# 4_2in_display.net
KiCad netlist of a schematic drawn in EAGLE
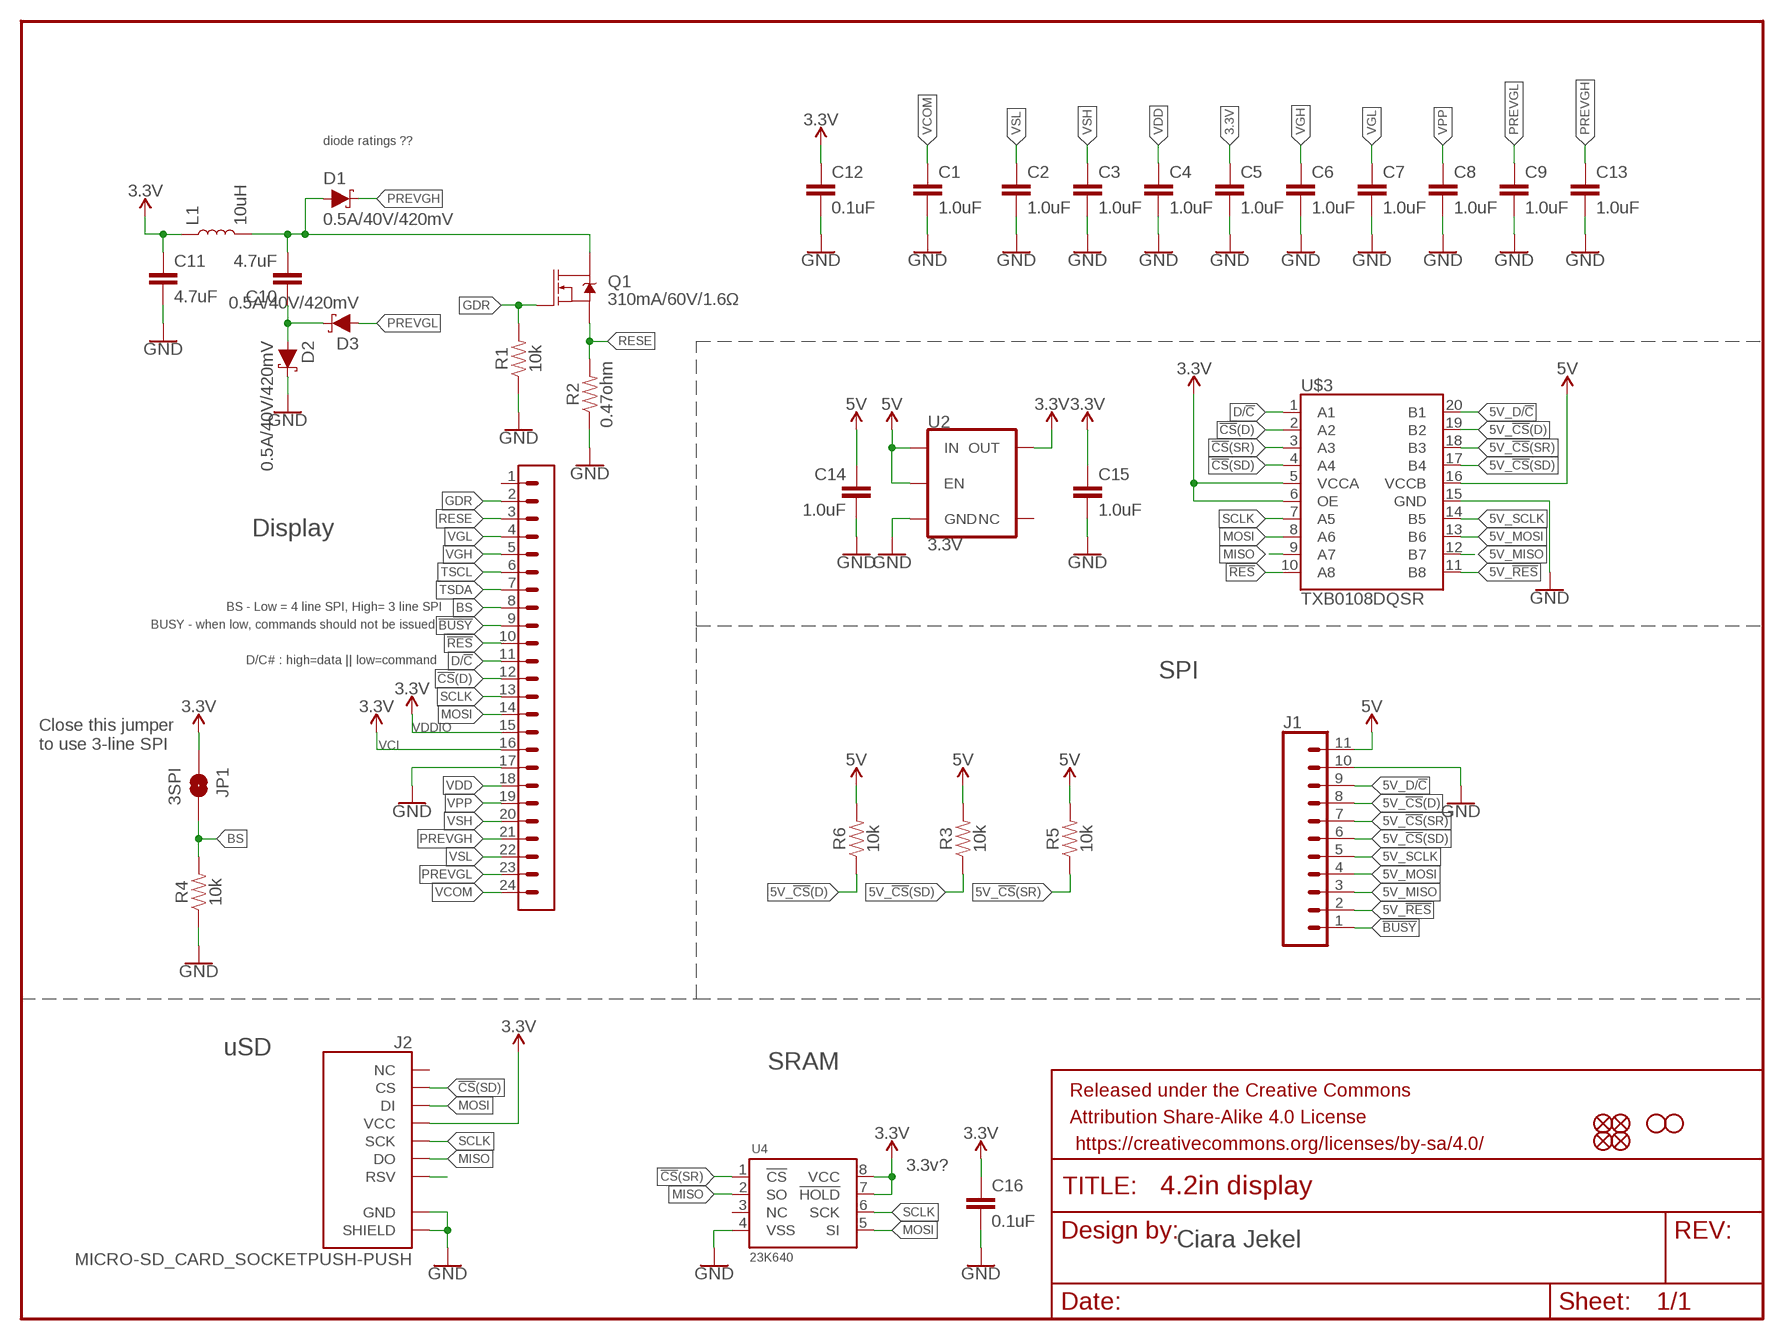
[diagram p0: schematic, sheet 1]

(export (version "E")
  (design (tool "Eeschema 10.0.6"))
  (components
    (comp (ref "C1")
      (value "1.0uF")
      (footprint "eagle-import:0603")
      (libsource (lib "eagle-import") (part "1.0UF-0603-16V-10%"))
    )
    (comp (ref "C2")
      (value "1.0uF")
      (footprint "eagle-import:0805")
      (libsource (lib "eagle-import") (part "1.0UF-0805-25V-10%"))
    )
    (comp (ref "C3")
      (value "1.0uF")
      (footprint "eagle-import:0805")
      (libsource (lib "eagle-import") (part "1.0UF-0805-25V-10%"))
    )
    (comp (ref "C4")
      (value "1.0uF")
      (footprint "eagle-import:0805")
      (libsource (lib "eagle-import") (part "1.0UF-0805-25V-10%"))
    )
    (comp (ref "C5")
      (value "1.0uF")
      (footprint "eagle-import:0805")
      (libsource (lib "eagle-import") (part "1.0UF-0805-25V-10%"))
    )
    (comp (ref "C6")
      (value "1.0uF")
      (footprint "eagle-import:0805")
      (libsource (lib "eagle-import") (part "1.0UF-0805-25V-10%"))
    )
    (comp (ref "C7")
      (value "1.0uF")
      (footprint "eagle-import:0805")
      (libsource (lib "eagle-import") (part "1.0UF-0805-25V-10%"))
    )
    (comp (ref "C8")
      (value "1.0uF")
      (footprint "eagle-import:0805")
      (libsource (lib "eagle-import") (part "1.0UF-0805-25V-10%"))
    )
    (comp (ref "C9")
      (value "1.0uF")
      (footprint "eagle-import:0805")
      (libsource (lib "eagle-import") (part "1.0UF-0805-25V-10%"))
    )
    (comp (ref "C10")
      (value "4.7uF")
      (footprint "eagle-import:0805")
      (libsource (lib "eagle-import") (part "22UF-0805-6.3V-20%"))
    )
    (comp (ref "C11")
      (value "4.7uF")
      (footprint "eagle-import:0805")
      (libsource (lib "eagle-import") (part "22UF-0805-6.3V-20%"))
    )
    (comp (ref "C12")
      (value "0.1uF")
      (footprint "eagle-import:0603")
      (libsource (lib "eagle-import") (part "0.1UF-0603-25V-(+80/-20%)"))
    )
    (comp (ref "C13")
      (value "1.0uF")
      (footprint "eagle-import:0805")
      (libsource (lib "eagle-import") (part "1.0UF-0805-25V-10%"))
    )
    (comp (ref "C14")
      (value "1.0uF")
      (footprint "eagle-import:0603")
      (libsource (lib "eagle-import") (part "1.0UF-0603-16V-10%"))
    )
    (comp (ref "C15")
      (value "1.0uF")
      (footprint "eagle-import:0603")
      (libsource (lib "eagle-import") (part "1.0UF-0603-16V-10%"))
    )
    (comp (ref "C16")
      (value "0.1uF")
      (footprint "eagle-import:0603")
      (libsource (lib "eagle-import") (part "0.1UF-0603-25V-(+80/-20%)"))
    )
    (comp (ref "D1")
      (value "0.5A/40V/420mV")
      (footprint "eagle-import:SOD-323")
      (libsource (lib "eagle-import") (part "DIODE-SCHOTTKY-PMEG4005EJ"))
    )
    (comp (ref "D2")
      (value "0.5A/40V/420mV")
      (footprint "eagle-import:SOD-323")
      (libsource (lib "eagle-import") (part "DIODE-SCHOTTKY-PMEG4005EJ"))
    )
    (comp (ref "D3")
      (value "0.5A/40V/420mV")
      (footprint "eagle-import:SOD-323")
      (libsource (lib "eagle-import") (part "DIODE-SCHOTTKY-PMEG4005EJ"))
    )
    (comp (ref "FD1")
      (value "FIDUCIALUFIDUCIAL")
      (footprint "eagle-import:FIDUCIAL-MICRO")
      (libsource (lib "eagle-import") (part "FIDUCIALUFIDUCIAL"))
    )
    (comp (ref "FD2")
      (value "FIDUCIALUFIDUCIAL")
      (footprint "eagle-import:FIDUCIAL-MICRO")
      (libsource (lib "eagle-import") (part "FIDUCIALUFIDUCIAL"))
    )
    (comp (ref "FD3")
      (value "FIDUCIALUFIDUCIAL")
      (footprint "eagle-import:FIDUCIAL-MICRO")
      (libsource (lib "eagle-import") (part "FIDUCIALUFIDUCIAL"))
    )
    (comp (ref "FD4")
      (value "FIDUCIALUFIDUCIAL")
      (footprint "eagle-import:FIDUCIAL-MICRO")
      (libsource (lib "eagle-import") (part "FIDUCIALUFIDUCIAL"))
    )
    (comp (ref "FRAME1")
      (value "FRAME-LETTER")
      (footprint "eagle-import:CREATIVE_COMMONS")
      (libsource (lib "eagle-import") (part "FRAME-LETTER"))
    )
    (comp (ref "H1")
      (value "STAND-OFF")
      (footprint "eagle-import:STAND-OFF")
      (libsource (lib "eagle-import") (part "STAND-OFF"))
    )
    (comp (ref "H2")
      (value "STAND-OFF")
      (footprint "eagle-import:STAND-OFF")
      (libsource (lib "eagle-import") (part "STAND-OFF"))
    )
    (comp (ref "J1")
      (value "CONN_111X11_NO_SILK")
      (footprint "eagle-import:1X11_NO_SILK")
      (libsource (lib "eagle-import") (part "CONN_111X11_NO_SILK"))
    )
    (comp (ref "J2")
      (value "MICRO-SD_CARD_SOCKETPUSH-PUSH")
      (footprint "eagle-import:MICRO-SD-SOCKET")
      (libsource (lib "eagle-import") (part "MICRO-SD_CARD_SOCKETPUSH-PUSH"))
    )
    (comp (ref "JP1")
      (value "3SPI")
      (footprint "eagle-import:SMT-JUMPER_2_NO_SILK")
      (libsource (lib "eagle-import") (part "JUMPER-SMT_2_NO_SILK"))
    )
    (comp (ref "L1")
      (value "10uH")
      (footprint "eagle-import:INDUCTOR_4.7UH")
      (libsource (lib "eagle-import") (part "INDUCTOR-CDRH-10UH"))
    )
    (comp (ref "Q1")
      (value "310mA/60V/1.6Ω")
      (footprint "eagle-import:SOT323")
      (libsource (lib "eagle-import") (part "MOSFET-NCH-2N7002PW"))
    )
    (comp (ref "R1")
      (value "10k")
      (footprint "eagle-import:0603")
      (libsource (lib "eagle-import") (part "10KOHM-0603-1/10W-1%"))
    )
    (comp (ref "R2")
      (value "0.47ohm")
      (footprint "eagle-import:0603")
      (libsource (lib "eagle-import") (part "RESISTOR0603"))
    )
    (comp (ref "R3")
      (value "10k")
      (footprint "eagle-import:0603")
      (libsource (lib "eagle-import") (part "10KOHM-0603-1/10W-1%"))
    )
    (comp (ref "R4")
      (value "10k")
      (footprint "eagle-import:0603")
      (libsource (lib "eagle-import") (part "10KOHM-0603-1/10W-1%"))
    )
    (comp (ref "R5")
      (value "10k")
      (footprint "eagle-import:0603")
      (libsource (lib "eagle-import") (part "10KOHM-0603-1/10W-1%"))
    )
    (comp (ref "R6")
      (value "10k")
      (footprint "eagle-import:0603")
      (libsource (lib "eagle-import") (part "10KOHM-0603-1/10W-1%"))
    )
    (comp (ref "U$1")
      (value "24_PIN_FPC_0.5MM")
      (footprint "eagle-import:24_PIN_FPC_0.5MM")
      (libsource (lib "eagle-import") (part "24_PIN_FPC_0.5MM"))
    )
    (comp (ref "U$3")
      (value "TXB0108DQSR")
      (footprint "eagle-import:UFDFN-20")
      (libsource (lib "eagle-import") (part "TXB0108"))
    )
    (comp (ref "U2")
      (value "3.3V")
      (footprint "eagle-import:SOT23-5")
      (libsource (lib "eagle-import") (part "V_REG_AP2112K-3.3V"))
    )
    (comp (ref "U4")
      (value "23K640")
      (footprint "eagle-import:SO08")
      (libsource (lib "eagle-import") (part "23K640"))
    )
  )
  (nets
    (net (code "1") (name "/5V_D{slash}~{C}") (class "Default")
      (node (ref "J1") (pin "9") (pinfunction "9_9") (pintype "passive"))
      (node (ref "U$3") (pin "20") (pinfunction "B1_20") (pintype "bidirectional"))
    )
    (net (code "2") (name "/5V_~{CS}(D)") (class "Default")
      (node (ref "J1") (pin "8") (pinfunction "8_8") (pintype "passive"))
      (node (ref "R6") (pin "1") (pinfunction "1_1") (pintype "passive"))
      (node (ref "U$3") (pin "19") (pinfunction "B2_19") (pintype "bidirectional"))
    )
    (net (code "3") (name "/5V_~{CS}(SD)") (class "Default")
      (node (ref "J1") (pin "6") (pinfunction "6_6") (pintype "passive"))
      (node (ref "R3") (pin "1") (pinfunction "1_1") (pintype "passive"))
      (node (ref "U$3") (pin "17") (pinfunction "B4_17") (pintype "bidirectional"))
    )
    (net (code "4") (name "/5V_~{CS}(SR)") (class "Default")
      (node (ref "J1") (pin "7") (pinfunction "7_7") (pintype "passive"))
      (node (ref "R5") (pin "1") (pinfunction "1_1") (pintype "passive"))
      (node (ref "U$3") (pin "18") (pinfunction "B3_18") (pintype "bidirectional"))
    )
    (net (code "5") (name "/5V_~{RES}") (class "Default")
      (node (ref "J1") (pin "2") (pinfunction "2_2") (pintype "passive"))
      (node (ref "U$3") (pin "11") (pinfunction "B8_11") (pintype "bidirectional"))
    )
    (net (code "6") (name "/D{slash}~{C}") (class "Default")
      (node (ref "U$1") (pin "11") (pinfunction "11_11") (pintype "bidirectional"))
      (node (ref "U$3") (pin "1") (pinfunction "A1_1") (pintype "bidirectional"))
    )
    (net (code "7") (name "/~{BUSY}") (class "Default")
      (node (ref "J1") (pin "1") (pinfunction "1_1") (pintype "passive"))
      (node (ref "U$1") (pin "9") (pinfunction "9_9") (pintype "bidirectional"))
    )
    (net (code "8") (name "/~{CS}(D)") (class "Default")
      (node (ref "U$1") (pin "12") (pinfunction "12_12") (pintype "bidirectional"))
      (node (ref "U$3") (pin "2") (pinfunction "A2_2") (pintype "bidirectional"))
    )
    (net (code "9") (name "/~{CS}(SD)") (class "Default")
      (node (ref "J2") (pin "CS") (pinfunction "CS_CS") (pintype "bidirectional"))
      (node (ref "U$3") (pin "4") (pinfunction "A4_4") (pintype "bidirectional"))
    )
    (net (code "10") (name "/~{CS}(SR)") (class "Default")
      (node (ref "U$3") (pin "3") (pinfunction "A3_3") (pintype "bidirectional"))
      (node (ref "U4") (pin "1") (pinfunction "~{CS}_1") (pintype "bidirectional"))
    )
    (net (code "11") (name "/~{RES}") (class "Default")
      (node (ref "U$1") (pin "10") (pinfunction "10_10") (pintype "bidirectional"))
      (node (ref "U$3") (pin "10") (pinfunction "A8_10") (pintype "bidirectional"))
    )
    (net (code "12") (name "3.3V") (class "Default")
      (node (ref "C11") (pin "1") (pinfunction "1_1") (pintype "passive"))
      (node (ref "C12") (pin "1") (pinfunction "1_1") (pintype "passive"))
      (node (ref "C15") (pin "1") (pinfunction "1_1") (pintype "passive"))
      (node (ref "C16") (pin "1") (pinfunction "1_1") (pintype "passive"))
      (node (ref "C5") (pin "1") (pinfunction "1_1") (pintype "passive"))
      (node (ref "J2") (pin "VCC") (pinfunction "VCC_VCC") (pintype "bidirectional"))
      (node (ref "JP1") (pin "1") (pinfunction "1_1") (pintype "passive"))
      (node (ref "L1") (pin "P$1") (pinfunction "1_P$1") (pintype "passive"))
      (node (ref "U$1") (pin "15") (pinfunction "15_15") (pintype "bidirectional"))
      (node (ref "U$1") (pin "16") (pinfunction "16_16") (pintype "bidirectional"))
      (node (ref "U$3") (pin "5") (pinfunction "VCCA_5") (pintype "bidirectional"))
      (node (ref "U$3") (pin "6") (pinfunction "OE_6") (pintype "bidirectional"))
      (node (ref "U2") (pin "5") (pinfunction "OUT_5") (pintype "passive"))
      (node (ref "U4") (pin "7") (pinfunction "~{HOLD}_7") (pintype "bidirectional"))
      (node (ref "U4") (pin "8") (pinfunction "VCC_8") (pintype "bidirectional"))
    )
    (net (code "13") (name "5V") (class "Default")
      (node (ref "C14") (pin "1") (pinfunction "1_1") (pintype "passive"))
      (node (ref "J1") (pin "11") (pinfunction "11_11") (pintype "passive"))
      (node (ref "R3") (pin "2") (pinfunction "2_2") (pintype "passive"))
      (node (ref "R5") (pin "2") (pinfunction "2_2") (pintype "passive"))
      (node (ref "R6") (pin "2") (pinfunction "2_2") (pintype "passive"))
      (node (ref "U$3") (pin "16") (pinfunction "VCCB_16") (pintype "bidirectional"))
      (node (ref "U2") (pin "1") (pinfunction "IN_1") (pintype "input"))
      (node (ref "U2") (pin "3") (pinfunction "EN_3") (pintype "input"))
    )
    (net (code "14") (name "5V_MISO") (class "Default")
      (node (ref "J1") (pin "3") (pinfunction "3_3") (pintype "passive"))
      (node (ref "U$3") (pin "12") (pinfunction "B7_12") (pintype "bidirectional"))
    )
    (net (code "15") (name "5V_MOSI") (class "Default")
      (node (ref "J1") (pin "4") (pinfunction "4_4") (pintype "passive"))
      (node (ref "U$3") (pin "13") (pinfunction "B6_13") (pintype "bidirectional"))
    )
    (net (code "16") (name "5V_SCLK") (class "Default")
      (node (ref "J1") (pin "5") (pinfunction "5_5") (pintype "passive"))
      (node (ref "U$3") (pin "14") (pinfunction "B5_14") (pintype "bidirectional"))
    )
    (net (code "17") (name "BS") (class "Default")
      (node (ref "JP1") (pin "2") (pinfunction "2_2") (pintype "passive"))
      (node (ref "R4") (pin "2") (pinfunction "2_2") (pintype "passive"))
      (node (ref "U$1") (pin "8") (pinfunction "8_8") (pintype "bidirectional"))
    )
    (net (code "18") (name "GDR") (class "Default")
      (node (ref "Q1") (pin "1") (pinfunction "G_1") (pintype "bidirectional"))
      (node (ref "R1") (pin "2") (pinfunction "2_2") (pintype "passive"))
      (node (ref "U$1") (pin "2") (pinfunction "2_2") (pintype "bidirectional"))
    )
    (net (code "19") (name "GND") (class "Default")
      (node (ref "C1") (pin "2") (pinfunction "2_2") (pintype "passive"))
      (node (ref "C11") (pin "2") (pinfunction "2_2") (pintype "passive"))
      (node (ref "C12") (pin "2") (pinfunction "2_2") (pintype "passive"))
      (node (ref "C13") (pin "2") (pinfunction "2_2") (pintype "passive"))
      (node (ref "C14") (pin "2") (pinfunction "2_2") (pintype "passive"))
      (node (ref "C15") (pin "2") (pinfunction "2_2") (pintype "passive"))
      (node (ref "C16") (pin "2") (pinfunction "2_2") (pintype "passive"))
      (node (ref "C2") (pin "2") (pinfunction "2_2") (pintype "passive"))
      (node (ref "C3") (pin "2") (pinfunction "2_2") (pintype "passive"))
      (node (ref "C4") (pin "2") (pinfunction "2_2") (pintype "passive"))
      (node (ref "C5") (pin "2") (pinfunction "2_2") (pintype "passive"))
      (node (ref "C6") (pin "2") (pinfunction "2_2") (pintype "passive"))
      (node (ref "C7") (pin "2") (pinfunction "2_2") (pintype "passive"))
      (node (ref "C8") (pin "2") (pinfunction "2_2") (pintype "passive"))
      (node (ref "C9") (pin "2") (pinfunction "2_2") (pintype "passive"))
      (node (ref "D2") (pin "C") (pinfunction "C_C") (pintype "passive"))
      (node (ref "J1") (pin "10") (pinfunction "10_10") (pintype "passive"))
      (node (ref "J2") (pin "CD1") (pinfunction "SHIELD_CD1") (pintype "bidirectional"))
      (node (ref "J2") (pin "GND") (pinfunction "GND_GND") (pintype "bidirectional"))
      (node (ref "R1") (pin "1") (pinfunction "1_1") (pintype "passive"))
      (node (ref "R2") (pin "1") (pinfunction "1_1") (pintype "passive"))
      (node (ref "R4") (pin "1") (pinfunction "1_1") (pintype "passive"))
      (node (ref "U$1") (pin "17") (pinfunction "17_17") (pintype "bidirectional"))
      (node (ref "U$3") (pin "15") (pinfunction "GND_15") (pintype "bidirectional"))
      (node (ref "U2") (pin "2") (pinfunction "GND_2") (pintype "input"))
      (node (ref "U4") (pin "4") (pinfunction "VSS_4") (pintype "bidirectional"))
    )
    (net (code "20") (name "MISO") (class "Default")
      (node (ref "J2") (pin "DO") (pinfunction "DO_DO") (pintype "bidirectional"))
      (node (ref "U$3") (pin "9") (pinfunction "A7_9") (pintype "bidirectional"))
      (node (ref "U4") (pin "2") (pinfunction "SO_2") (pintype "bidirectional"))
    )
    (net (code "21") (name "MOSI") (class "Default")
      (node (ref "J2") (pin "DI") (pinfunction "DI_DI") (pintype "bidirectional"))
      (node (ref "U$1") (pin "14") (pinfunction "14_14") (pintype "bidirectional"))
      (node (ref "U$3") (pin "8") (pinfunction "A6_8") (pintype "bidirectional"))
      (node (ref "U4") (pin "5") (pinfunction "SI_5") (pintype "bidirectional"))
    )
    (net (code "22") (name "Net-(C10-Pad1)") (class "Default")
      (node (ref "C10") (pin "1") (pinfunction "1_1") (pintype "passive"))
      (node (ref "D2") (pin "A") (pinfunction "A_A") (pintype "passive"))
      (node (ref "D3") (pin "C") (pinfunction "C_C") (pintype "passive"))
    )
    (net (code "23") (name "Net-(L1-2)") (class "Default")
      (node (ref "C10") (pin "2") (pinfunction "2_2") (pintype "passive"))
      (node (ref "D1") (pin "A") (pinfunction "A_A") (pintype "passive"))
      (node (ref "L1") (pin "P$2") (pinfunction "2_P$2") (pintype "passive"))
      (node (ref "Q1") (pin "3") (pinfunction "D_3") (pintype "bidirectional"))
    )
    (net (code "24") (name "PREVGH") (class "Default")
      (node (ref "C13") (pin "1") (pinfunction "1_1") (pintype "passive"))
      (node (ref "D1") (pin "C") (pinfunction "C_C") (pintype "passive"))
      (node (ref "U$1") (pin "21") (pinfunction "21_21") (pintype "bidirectional"))
    )
    (net (code "25") (name "PREVGL") (class "Default")
      (node (ref "C9") (pin "1") (pinfunction "1_1") (pintype "passive"))
      (node (ref "D3") (pin "A") (pinfunction "A_A") (pintype "passive"))
      (node (ref "U$1") (pin "23") (pinfunction "23_23") (pintype "bidirectional"))
    )
    (net (code "26") (name "RESE") (class "Default")
      (node (ref "Q1") (pin "2") (pinfunction "S_2") (pintype "bidirectional"))
      (node (ref "R2") (pin "2") (pinfunction "2_2") (pintype "passive"))
      (node (ref "U$1") (pin "3") (pinfunction "3_3") (pintype "bidirectional"))
    )
    (net (code "27") (name "SCLK") (class "Default")
      (node (ref "J2") (pin "SCLK") (pinfunction "SCK_SCLK") (pintype "bidirectional"))
      (node (ref "U$1") (pin "13") (pinfunction "13_13") (pintype "bidirectional"))
      (node (ref "U$3") (pin "7") (pinfunction "A5_7") (pintype "bidirectional"))
      (node (ref "U4") (pin "6") (pinfunction "SCK_6") (pintype "bidirectional"))
    )
    (net (code "28") (name "TSCL") (class "Default")
      (node (ref "U$1") (pin "6") (pinfunction "6_6") (pintype "bidirectional"))
    )
    (net (code "29") (name "TSDA") (class "Default")
      (node (ref "U$1") (pin "7") (pinfunction "7_7") (pintype "bidirectional"))
    )
    (net (code "30") (name "VCOM") (class "Default")
      (node (ref "C1") (pin "1") (pinfunction "1_1") (pintype "passive"))
      (node (ref "U$1") (pin "24") (pinfunction "24_24") (pintype "bidirectional"))
    )
    (net (code "31") (name "VDD") (class "Default")
      (node (ref "C4") (pin "1") (pinfunction "1_1") (pintype "passive"))
      (node (ref "U$1") (pin "18") (pinfunction "18_18") (pintype "bidirectional"))
    )
    (net (code "32") (name "VGH") (class "Default")
      (node (ref "C6") (pin "1") (pinfunction "1_1") (pintype "passive"))
      (node (ref "U$1") (pin "5") (pinfunction "5_5") (pintype "bidirectional"))
    )
    (net (code "33") (name "VGL") (class "Default")
      (node (ref "C7") (pin "1") (pinfunction "1_1") (pintype "passive"))
      (node (ref "U$1") (pin "4") (pinfunction "4_4") (pintype "bidirectional"))
    )
    (net (code "34") (name "VPP") (class "Default")
      (node (ref "C8") (pin "1") (pinfunction "1_1") (pintype "passive"))
      (node (ref "U$1") (pin "19") (pinfunction "19_19") (pintype "bidirectional"))
    )
    (net (code "35") (name "VSH") (class "Default")
      (node (ref "C3") (pin "1") (pinfunction "1_1") (pintype "passive"))
      (node (ref "U$1") (pin "20") (pinfunction "20_20") (pintype "bidirectional"))
    )
    (net (code "36") (name "VSL") (class "Default")
      (node (ref "C2") (pin "1") (pinfunction "1_1") (pintype "passive"))
      (node (ref "U$1") (pin "22") (pinfunction "22_22") (pintype "bidirectional"))
    )
    (net (code "37") (name "unconnected-(J2-NC-PadRSV2)") (class "Default")
      (node (ref "J2") (pin "RSV2") (pinfunction "NC_RSV2") (pintype "bidirectional"))
    )
    (net (code "38") (name "unconnected-(J2-RSV-PadRSV1)") (class "Default")
      (node (ref "J2") (pin "RSV1") (pinfunction "RSV_RSV1") (pintype "bidirectional"))
    )
    (net (code "39") (name "unconnected-(U$1-Pad1)") (class "Default")
      (node (ref "U$1") (pin "1") (pinfunction "1_1") (pintype "bidirectional"))
    )
    (net (code "40") (name "unconnected-(U2-NC-Pad4)") (class "Default")
      (node (ref "U2") (pin "4") (pinfunction "NC_4") (pintype "no_connect"))
    )
    (net (code "41") (name "unconnected-(U4-NC-Pad3)") (class "Default")
      (node (ref "U4") (pin "3") (pinfunction "NC_3") (pintype "bidirectional"))
    )
  )
)
